# LIDO-HW_200_MCU_Peripherals_2.net
KiCad netlist of a schematic drawn in Altium Designer
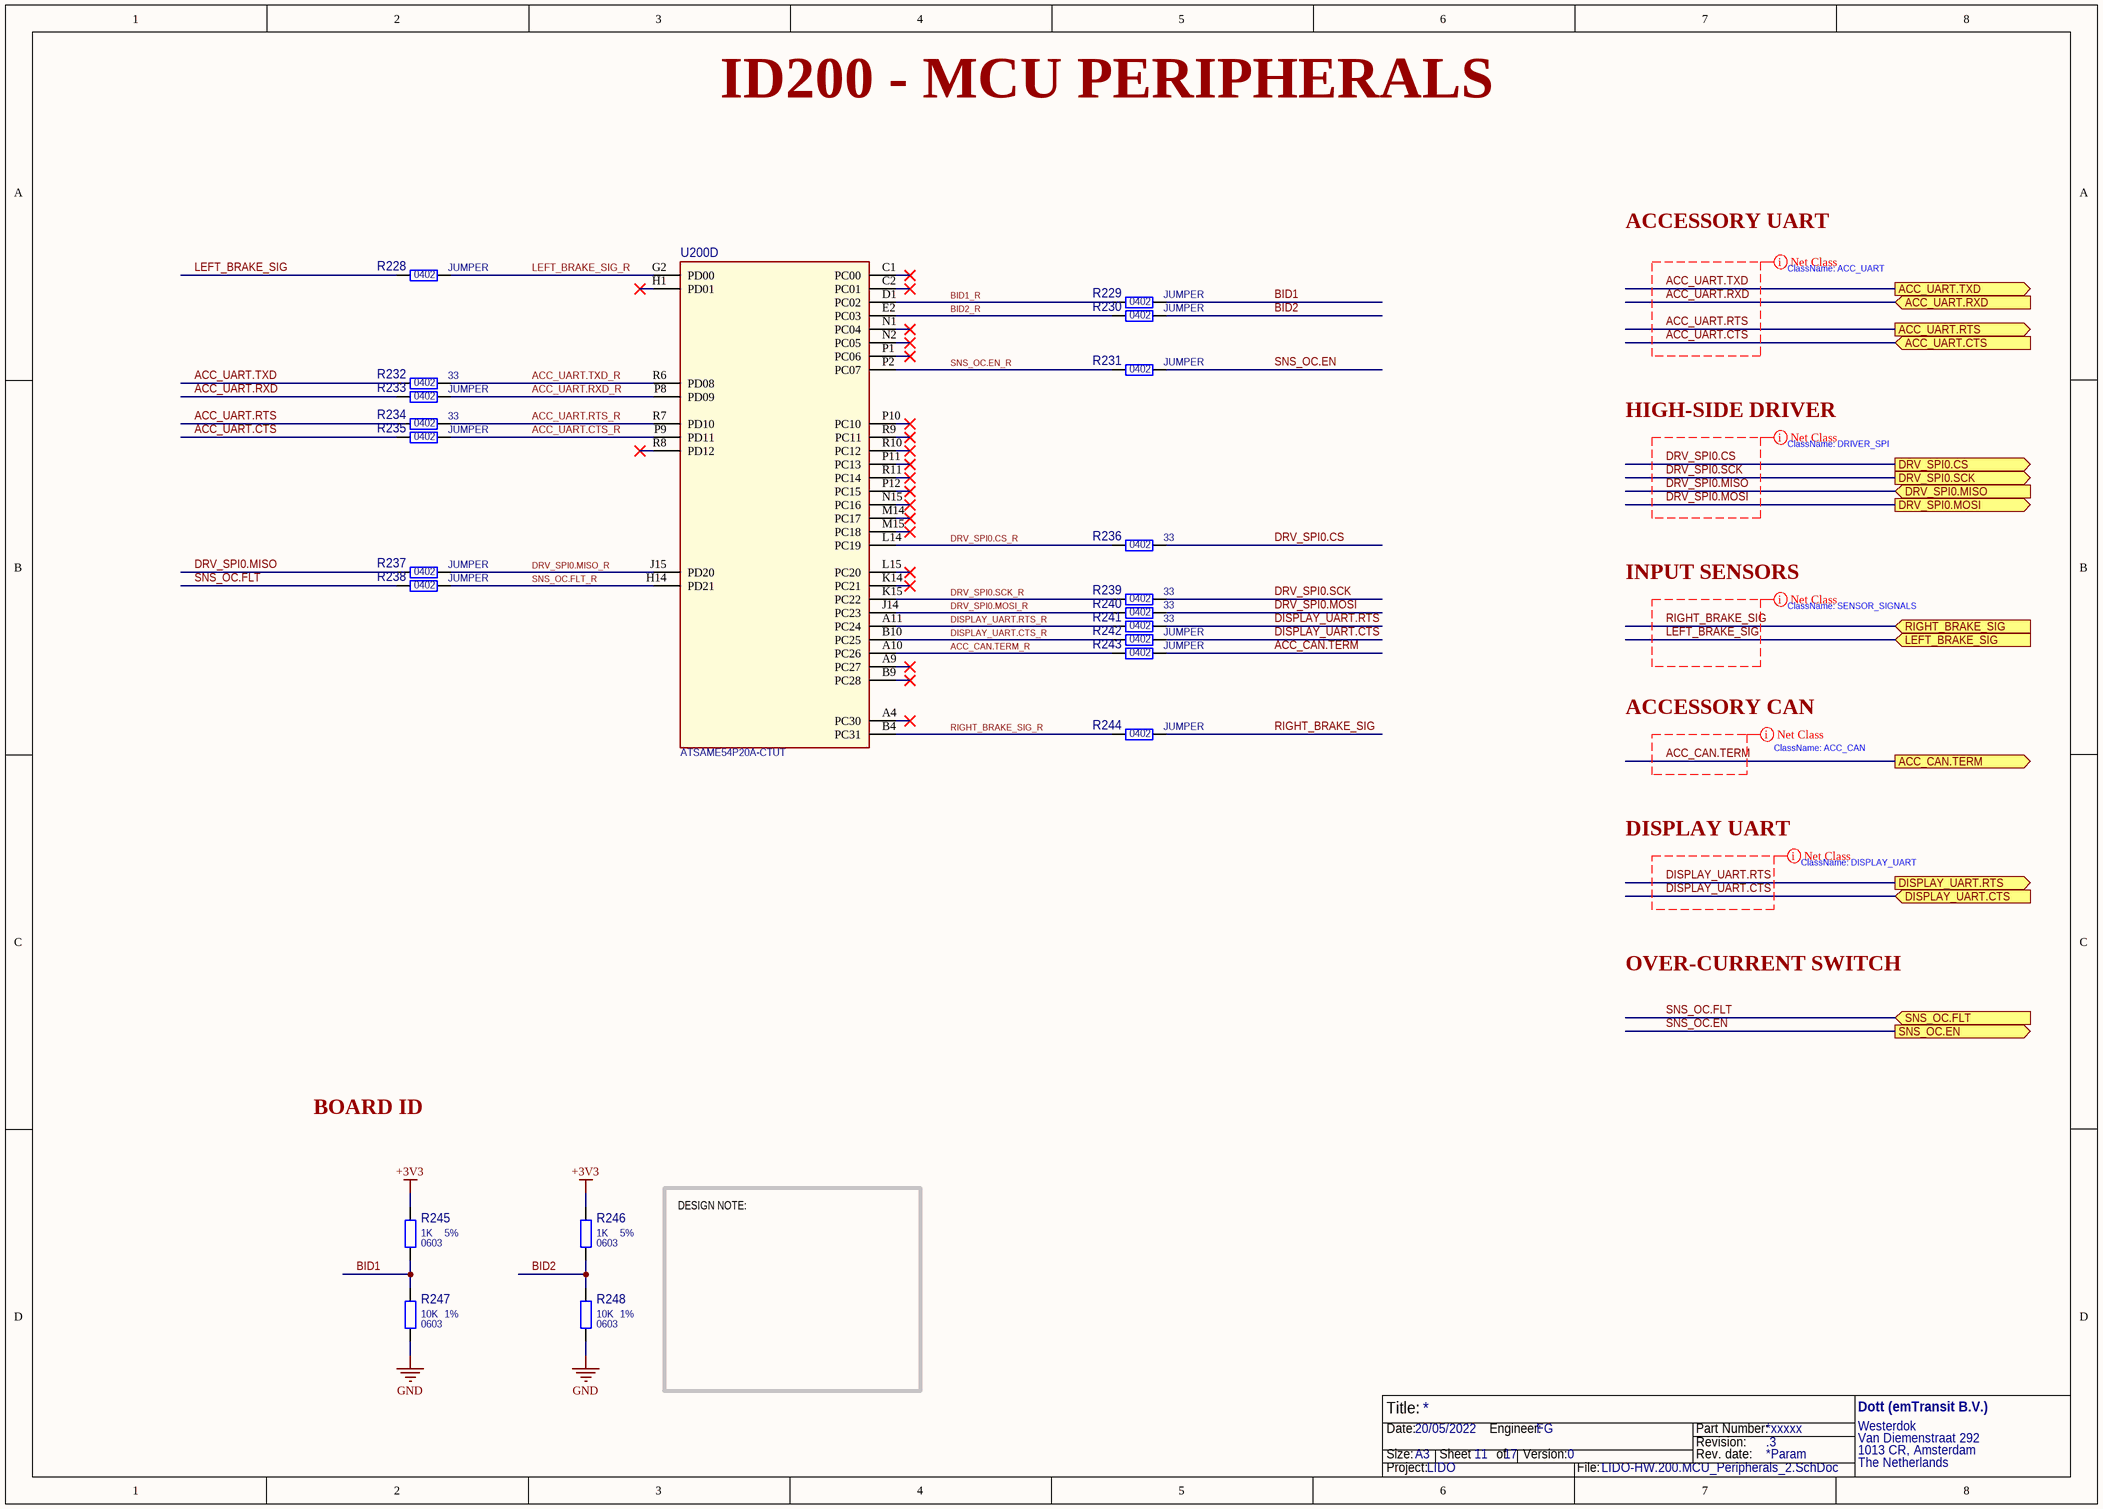
[diagram p0: LIDO-HW.200.MCU_Peripherals_2.SchDoc]

(export (version "E")
  (design (tool "Eeschema 10.0.6"))
  (components
    (comp (ref "R228")
      (value "JUMPER")
      (footprint "RES_0402_1005X40-N_YAGEO_A")
      (description "RES SMD 0 OHM JUMPER 1/10W 0402")
      (fields
        (field (name "MANUFACTURER PART NUMBER") "ERJ-2GE0R00X")
        (field (name "MANUFACTURER") "Panasonic Electronic Components")
        (field (name "PART PACKAGE") "0402")
      )
      (libsource (lib "DB_Library") (part "Resistor"))
    )
    (comp (ref "R229")
      (value "JUMPER")
      (footprint "RES_0402_1005X40-N_YAGEO_A")
      (description "RES SMD 0 OHM JUMPER 1/10W 0402")
      (fields
        (field (name "MANUFACTURER PART NUMBER") "ERJ-2GE0R00X")
        (field (name "MANUFACTURER") "Panasonic Electronic Components")
        (field (name "PART PACKAGE") "0402")
      )
      (libsource (lib "DB_Library") (part "Resistor"))
    )
    (comp (ref "R230")
      (value "JUMPER")
      (footprint "RES_0402_1005X40-N_YAGEO_A")
      (description "RES SMD 0 OHM JUMPER 1/10W 0402")
      (fields
        (field (name "MANUFACTURER PART NUMBER") "ERJ-2GE0R00X")
        (field (name "MANUFACTURER") "Panasonic Electronic Components")
        (field (name "PART PACKAGE") "0402")
      )
      (libsource (lib "DB_Library") (part "Resistor"))
    )
    (comp (ref "R231")
      (value "JUMPER")
      (footprint "RES_0402_1005X40-N_YAGEO_A")
      (description "RES SMD 0 OHM JUMPER 1/10W 0402")
      (fields
        (field (name "MANUFACTURER PART NUMBER") "ERJ-2GE0R00X")
        (field (name "MANUFACTURER") "Panasonic Electronic Components")
        (field (name "PART PACKAGE") "0402")
      )
      (libsource (lib "DB_Library") (part "Resistor"))
    )
    (comp (ref "R232")
      (value "33")
      (footprint "RES_0402_1005X40-N_YAGEO_A")
      (description "RES SMD 33 OHM 5% 1/10W 0402")
      (fields
        (field (name "MANUFACTURER PART NUMBER") "ERJ-2GEJ330X")
        (field (name "MANUFACTURER") "Panasonic Electronic Components")
        (field (name "PART PACKAGE") "0402")
      )
      (libsource (lib "DB_Library") (part "Resistor"))
    )
    (comp (ref "R233")
      (value "JUMPER")
      (footprint "RES_0402_1005X40-N_YAGEO_A")
      (description "RES SMD 0 OHM JUMPER 1/10W 0402")
      (fields
        (field (name "MANUFACTURER PART NUMBER") "ERJ-2GE0R00X")
        (field (name "MANUFACTURER") "Panasonic Electronic Components")
        (field (name "PART PACKAGE") "0402")
      )
      (libsource (lib "DB_Library") (part "Resistor"))
    )
    (comp (ref "R234")
      (value "33")
      (footprint "RES_0402_1005X40-N_YAGEO_A")
      (description "RES SMD 33 OHM 5% 1/10W 0402")
      (fields
        (field (name "MANUFACTURER PART NUMBER") "ERJ-2GEJ330X")
        (field (name "MANUFACTURER") "Panasonic Electronic Components")
        (field (name "PART PACKAGE") "0402")
      )
      (libsource (lib "DB_Library") (part "Resistor"))
    )
    (comp (ref "R235")
      (value "JUMPER")
      (footprint "RES_0402_1005X40-N_YAGEO_A")
      (description "RES SMD 0 OHM JUMPER 1/10W 0402")
      (fields
        (field (name "MANUFACTURER PART NUMBER") "ERJ-2GE0R00X")
        (field (name "MANUFACTURER") "Panasonic Electronic Components")
        (field (name "PART PACKAGE") "0402")
      )
      (libsource (lib "DB_Library") (part "Resistor"))
    )
    (comp (ref "R236")
      (value "33")
      (footprint "RES_0402_1005X40-N_YAGEO_A")
      (description "RES SMD 33 OHM 5% 1/10W 0402")
      (fields
        (field (name "MANUFACTURER PART NUMBER") "ERJ-2GEJ330X")
        (field (name "MANUFACTURER") "Panasonic Electronic Components")
        (field (name "PART PACKAGE") "0402")
      )
      (libsource (lib "DB_Library") (part "Resistor"))
    )
    (comp (ref "R237")
      (value "JUMPER")
      (footprint "RES_0402_1005X40-N_YAGEO_A")
      (description "RES SMD 0 OHM JUMPER 1/10W 0402")
      (fields
        (field (name "MANUFACTURER PART NUMBER") "ERJ-2GE0R00X")
        (field (name "MANUFACTURER") "Panasonic Electronic Components")
        (field (name "PART PACKAGE") "0402")
      )
      (libsource (lib "DB_Library") (part "Resistor"))
    )
    (comp (ref "R238")
      (value "JUMPER")
      (footprint "RES_0402_1005X40-N_YAGEO_A")
      (description "RES SMD 0 OHM JUMPER 1/10W 0402")
      (fields
        (field (name "MANUFACTURER PART NUMBER") "ERJ-2GE0R00X")
        (field (name "MANUFACTURER") "Panasonic Electronic Components")
        (field (name "PART PACKAGE") "0402")
      )
      (libsource (lib "DB_Library") (part "Resistor"))
    )
    (comp (ref "R239")
      (value "33")
      (footprint "RES_0402_1005X40-N_YAGEO_A")
      (description "RES SMD 33 OHM 5% 1/10W 0402")
      (fields
        (field (name "MANUFACTURER PART NUMBER") "ERJ-2GEJ330X")
        (field (name "MANUFACTURER") "Panasonic Electronic Components")
        (field (name "PART PACKAGE") "0402")
      )
      (libsource (lib "DB_Library") (part "Resistor"))
    )
    (comp (ref "R240")
      (value "33")
      (footprint "RES_0402_1005X40-N_YAGEO_A")
      (description "RES SMD 33 OHM 5% 1/10W 0402")
      (fields
        (field (name "MANUFACTURER PART NUMBER") "ERJ-2GEJ330X")
        (field (name "MANUFACTURER") "Panasonic Electronic Components")
        (field (name "PART PACKAGE") "0402")
      )
      (libsource (lib "DB_Library") (part "Resistor"))
    )
    (comp (ref "R241")
      (value "33")
      (footprint "RES_0402_1005X40-N_YAGEO_A")
      (description "RES SMD 33 OHM 5% 1/10W 0402")
      (fields
        (field (name "MANUFACTURER PART NUMBER") "ERJ-2GEJ330X")
        (field (name "MANUFACTURER") "Panasonic Electronic Components")
        (field (name "PART PACKAGE") "0402")
      )
      (libsource (lib "DB_Library") (part "Resistor"))
    )
    (comp (ref "R242")
      (value "JUMPER")
      (footprint "RES_0402_1005X40-N_YAGEO_A")
      (description "RES SMD 0 OHM JUMPER 1/10W 0402")
      (fields
        (field (name "MANUFACTURER PART NUMBER") "ERJ-2GE0R00X")
        (field (name "MANUFACTURER") "Panasonic Electronic Components")
        (field (name "PART PACKAGE") "0402")
      )
      (libsource (lib "DB_Library") (part "Resistor"))
    )
    (comp (ref "R243")
      (value "JUMPER")
      (footprint "RES_0402_1005X40-N_YAGEO_A")
      (description "RES SMD 0 OHM JUMPER 1/10W 0402")
      (fields
        (field (name "MANUFACTURER PART NUMBER") "ERJ-2GE0R00X")
        (field (name "MANUFACTURER") "Panasonic Electronic Components")
        (field (name "PART PACKAGE") "0402")
      )
      (libsource (lib "DB_Library") (part "Resistor"))
    )
    (comp (ref "R244")
      (value "JUMPER")
      (footprint "RES_0402_1005X40-N_YAGEO_A")
      (description "RES SMD 0 OHM JUMPER 1/10W 0402")
      (fields
        (field (name "MANUFACTURER PART NUMBER") "ERJ-2GE0R00X")
        (field (name "MANUFACTURER") "Panasonic Electronic Components")
        (field (name "PART PACKAGE") "0402")
      )
      (libsource (lib "DB_Library") (part "Resistor"))
    )
    (comp (ref "R245")
      (value "1K")
      (footprint "RES_0603_1608X60-N_YAGEO_A")
      (description "RES 1K OHM 5% 1/10W 0603")
      (fields
        (field (name "MANUFACTURER PART NUMBER") "RC0603JR-071KL")
        (field (name "MANUFACTURER") "YAGEO")
        (field (name "PART VALUE 2") "5%")
        (field (name "PART PACKAGE") "0603")
      )
      (libsource (lib "") (part "Resistor_1"))
    )
    (comp (ref "R246")
      (value "1K")
      (footprint "RES_0603_1608X60-N_YAGEO_A")
      (description "RES 1K OHM 5% 1/10W 0603")
      (fields
        (field (name "MANUFACTURER PART NUMBER") "RC0603JR-071KL")
        (field (name "MANUFACTURER") "YAGEO")
        (field (name "PART VALUE 2") "5%")
        (field (name "PART PACKAGE") "0603")
      )
      (libsource (lib "") (part "Resistor_1"))
    )
    (comp (ref "R247")
      (value "10K")
      (footprint "RES_0603_1608X60-N_YAGEO_A")
      (description "RES 10K OHM 1% 1/10W 0603")
      (fields
        (field (name "MANUFACTURER PART NUMBER") "RC0603FR-0710KL")
        (field (name "MANUFACTURER") "YAGEO")
        (field (name "PART VALUE 2") "1%")
        (field (name "PART PACKAGE") "0603")
      )
      (libsource (lib "") (part "Resistor_1"))
    )
    (comp (ref "R248")
      (value "10K")
      (footprint "RES_0603_1608X60-N_YAGEO_A")
      (description "RES 10K OHM 1% 1/10W 0603")
      (fields
        (field (name "MANUFACTURER PART NUMBER") "RC0603FR-0710KL")
        (field (name "MANUFACTURER") "YAGEO")
        (field (name "PART VALUE 2") "1%")
        (field (name "PART PACKAGE") "0603")
      )
      (libsource (lib "") (part "Resistor_1"))
    )
    (comp (ref "U200")
      (value "ATSAME54P20A-CTUT")
      (footprint "BGA120CP50_15X15_800X800X120B25-N_MICROCHIP_A")
      (fields (field (name "MANUFACTURER") "Microchip Technology") (field (name "OBSOLETE PART") "False"))
      (libsource (lib "DB_Library") (part "ATMEL_ATSAME54P20A-CT_A"))
    )
  )
  (nets
    (net (code "1") (name "+3V3") (class "Default")
      (node (ref "R245") (pin "2") (pinfunction "2_2") (pintype "passive"))
      (node (ref "R246") (pin "2") (pinfunction "2_2") (pintype "passive"))
    )
    (net (code "2") (name "/ACC_CAN.TERM") (class "Default")
      (node (ref "R243") (pin "2") (pinfunction "2_2") (pintype "passive"))
    )
    (net (code "3") (name "/ACC_CAN.TERM_R") (class "Default")
      (node (ref "R243") (pin "1") (pinfunction "1_1") (pintype "passive"))
      (node (ref "U200") (pin "A10") (pinfunction "PC26_A10") (pintype "passive"))
    )
    (net (code "4") (name "/ACC_UART.CTS") (class "Default")
      (node (ref "R235") (pin "1") (pinfunction "1_1") (pintype "passive"))
    )
    (net (code "5") (name "/ACC_UART.CTS_R") (class "Default")
      (node (ref "R235") (pin "2") (pinfunction "2_2") (pintype "passive"))
      (node (ref "U200") (pin "P9") (pinfunction "PD11_P9") (pintype "passive"))
    )
    (net (code "6") (name "/ACC_UART.RTS") (class "Default")
      (node (ref "R234") (pin "1") (pinfunction "1_1") (pintype "passive"))
    )
    (net (code "7") (name "/ACC_UART.RTS_R") (class "Default")
      (node (ref "R234") (pin "2") (pinfunction "2_2") (pintype "passive"))
      (node (ref "U200") (pin "R7") (pinfunction "PD10_R7") (pintype "passive"))
    )
    (net (code "8") (name "/ACC_UART.RXD") (class "Default")
      (node (ref "R233") (pin "1") (pinfunction "1_1") (pintype "passive"))
    )
    (net (code "9") (name "/ACC_UART.RXD_R") (class "Default")
      (node (ref "R233") (pin "2") (pinfunction "2_2") (pintype "passive"))
      (node (ref "U200") (pin "P8") (pinfunction "PD09_P8") (pintype "passive"))
    )
    (net (code "10") (name "/ACC_UART.TXD") (class "Default")
      (node (ref "R232") (pin "1") (pinfunction "1_1") (pintype "passive"))
    )
    (net (code "11") (name "/ACC_UART.TXD_R") (class "Default")
      (node (ref "R232") (pin "2") (pinfunction "2_2") (pintype "passive"))
      (node (ref "U200") (pin "R6") (pinfunction "PD08_R6") (pintype "passive"))
    )
    (net (code "12") (name "/BID1") (class "Default")
      (node (ref "R229") (pin "2") (pinfunction "2_2") (pintype "passive"))
      (node (ref "R245") (pin "1") (pinfunction "1_1") (pintype "passive"))
      (node (ref "R247") (pin "2") (pinfunction "2_2") (pintype "passive"))
    )
    (net (code "13") (name "/BID1_R") (class "Default")
      (node (ref "R229") (pin "1") (pinfunction "1_1") (pintype "passive"))
      (node (ref "U200") (pin "D1") (pinfunction "PC02_D1") (pintype "passive"))
    )
    (net (code "14") (name "/BID2") (class "Default")
      (node (ref "R230") (pin "2") (pinfunction "2_2") (pintype "passive"))
      (node (ref "R246") (pin "1") (pinfunction "1_1") (pintype "passive"))
      (node (ref "R248") (pin "2") (pinfunction "2_2") (pintype "passive"))
    )
    (net (code "15") (name "/BID2_R") (class "Default")
      (node (ref "R230") (pin "1") (pinfunction "1_1") (pintype "passive"))
      (node (ref "U200") (pin "E2") (pinfunction "PC03_E2") (pintype "passive"))
    )
    (net (code "16") (name "/DISPLAY_UART.CTS") (class "Default")
      (node (ref "R242") (pin "2") (pinfunction "2_2") (pintype "passive"))
    )
    (net (code "17") (name "/DISPLAY_UART.CTS_R") (class "Default")
      (node (ref "R242") (pin "1") (pinfunction "1_1") (pintype "passive"))
      (node (ref "U200") (pin "B10") (pinfunction "PC25_B10") (pintype "passive"))
    )
    (net (code "18") (name "/DISPLAY_UART.RTS") (class "Default")
      (node (ref "R241") (pin "2") (pinfunction "2_2") (pintype "passive"))
    )
    (net (code "19") (name "/DISPLAY_UART.RTS_R") (class "Default")
      (node (ref "R241") (pin "1") (pinfunction "1_1") (pintype "passive"))
      (node (ref "U200") (pin "A11") (pinfunction "PC24_A11") (pintype "passive"))
    )
    (net (code "20") (name "/DRV_SPI0.CS") (class "Default")
      (node (ref "R236") (pin "2") (pinfunction "2_2") (pintype "passive"))
    )
    (net (code "21") (name "/DRV_SPI0.CS_R") (class "Default")
      (node (ref "R236") (pin "1") (pinfunction "1_1") (pintype "passive"))
      (node (ref "U200") (pin "L14") (pinfunction "PC19_L14") (pintype "passive"))
    )
    (net (code "22") (name "/DRV_SPI0.MISO") (class "Default")
      (node (ref "R237") (pin "1") (pinfunction "1_1") (pintype "passive"))
    )
    (net (code "23") (name "/DRV_SPI0.MISO_R") (class "Default")
      (node (ref "R237") (pin "2") (pinfunction "2_2") (pintype "passive"))
      (node (ref "U200") (pin "J15") (pinfunction "PD20_J15") (pintype "passive"))
    )
    (net (code "24") (name "/DRV_SPI0.MOSI") (class "Default")
      (node (ref "R240") (pin "2") (pinfunction "2_2") (pintype "passive"))
    )
    (net (code "25") (name "/DRV_SPI0.MOSI_R") (class "Default")
      (node (ref "R240") (pin "1") (pinfunction "1_1") (pintype "passive"))
      (node (ref "U200") (pin "J14") (pinfunction "PC23_J14") (pintype "passive"))
    )
    (net (code "26") (name "/DRV_SPI0.SCK") (class "Default")
      (node (ref "R239") (pin "2") (pinfunction "2_2") (pintype "passive"))
    )
    (net (code "27") (name "/DRV_SPI0.SCK_R") (class "Default")
      (node (ref "R239") (pin "1") (pinfunction "1_1") (pintype "passive"))
      (node (ref "U200") (pin "K15") (pinfunction "PC22_K15") (pintype "passive"))
    )
    (net (code "28") (name "/LEFT_BRAKE_SIG") (class "Default")
      (node (ref "R228") (pin "1") (pinfunction "1_1") (pintype "passive"))
    )
    (net (code "29") (name "/LEFT_BRAKE_SIG_R") (class "Default")
      (node (ref "R228") (pin "2") (pinfunction "2_2") (pintype "passive"))
      (node (ref "U200") (pin "G2") (pinfunction "PD00_G2") (pintype "passive"))
    )
    (net (code "30") (name "/RIGHT_BRAKE_SIG") (class "Default")
      (node (ref "R244") (pin "2") (pinfunction "2_2") (pintype "passive"))
    )
    (net (code "31") (name "/RIGHT_BRAKE_SIG_R") (class "Default")
      (node (ref "R244") (pin "1") (pinfunction "1_1") (pintype "passive"))
      (node (ref "U200") (pin "B4") (pinfunction "PC31_B4") (pintype "passive"))
    )
    (net (code "32") (name "/SNS_OC.EN") (class "Default")
      (node (ref "R231") (pin "2") (pinfunction "2_2") (pintype "passive"))
    )
    (net (code "33") (name "/SNS_OC.EN_R") (class "Default")
      (node (ref "R231") (pin "1") (pinfunction "1_1") (pintype "passive"))
      (node (ref "U200") (pin "P2") (pinfunction "PC07_P2") (pintype "passive"))
    )
    (net (code "34") (name "/SNS_OC.FLT") (class "Default")
      (node (ref "R238") (pin "1") (pinfunction "1_1") (pintype "passive"))
    )
    (net (code "35") (name "/SNS_OC.FLT_R") (class "Default")
      (node (ref "R238") (pin "2") (pinfunction "2_2") (pintype "passive"))
      (node (ref "U200") (pin "H14") (pinfunction "PD21_H14") (pintype "passive"))
    )
    (net (code "36") (name "GND") (class "Default")
      (node (ref "R247") (pin "1") (pinfunction "1_1") (pintype "passive"))
      (node (ref "R248") (pin "1") (pinfunction "1_1") (pintype "passive"))
    )
    (net (code "37") (name "unconnected-(U200D-PC00-PadC1)") (class "Default")
      (node (ref "U200") (pin "C1") (pinfunction "PC00_C1") (pintype "passive+no_connect"))
    )
    (net (code "38") (name "unconnected-(U200D-PC01-PadC2)") (class "Default")
      (node (ref "U200") (pin "C2") (pinfunction "PC01_C2") (pintype "passive+no_connect"))
    )
    (net (code "39") (name "unconnected-(U200D-PC04-PadN1)") (class "Default")
      (node (ref "U200") (pin "N1") (pinfunction "PC04_N1") (pintype "passive+no_connect"))
    )
    (net (code "40") (name "unconnected-(U200D-PC05-PadN2)") (class "Default")
      (node (ref "U200") (pin "N2") (pinfunction "PC05_N2") (pintype "passive+no_connect"))
    )
    (net (code "41") (name "unconnected-(U200D-PC06-PadP1)") (class "Default")
      (node (ref "U200") (pin "P1") (pinfunction "PC06_P1") (pintype "passive+no_connect"))
    )
    (net (code "42") (name "unconnected-(U200D-PC10-PadP10)") (class "Default")
      (node (ref "U200") (pin "P10") (pinfunction "PC10_P10") (pintype "passive+no_connect"))
    )
    (net (code "43") (name "unconnected-(U200D-PC11-PadR9)") (class "Default")
      (node (ref "U200") (pin "R9") (pinfunction "PC11_R9") (pintype "passive+no_connect"))
    )
    (net (code "44") (name "unconnected-(U200D-PC12-PadR10)") (class "Default")
      (node (ref "U200") (pin "R10") (pinfunction "PC12_R10") (pintype "passive+no_connect"))
    )
    (net (code "45") (name "unconnected-(U200D-PC13-PadP11)") (class "Default")
      (node (ref "U200") (pin "P11") (pinfunction "PC13_P11") (pintype "passive+no_connect"))
    )
    (net (code "46") (name "unconnected-(U200D-PC14-PadR11)") (class "Default")
      (node (ref "U200") (pin "R11") (pinfunction "PC14_R11") (pintype "passive+no_connect"))
    )
    (net (code "47") (name "unconnected-(U200D-PC15-PadP12)") (class "Default")
      (node (ref "U200") (pin "P12") (pinfunction "PC15_P12") (pintype "passive+no_connect"))
    )
    (net (code "48") (name "unconnected-(U200D-PC16-PadN15)") (class "Default")
      (node (ref "U200") (pin "N15") (pinfunction "PC16_N15") (pintype "passive+no_connect"))
    )
    (net (code "49") (name "unconnected-(U200D-PC17-PadM14)") (class "Default")
      (node (ref "U200") (pin "M14") (pinfunction "PC17_M14") (pintype "passive+no_connect"))
    )
    (net (code "50") (name "unconnected-(U200D-PC18-PadM15)") (class "Default")
      (node (ref "U200") (pin "M15") (pinfunction "PC18_M15") (pintype "passive+no_connect"))
    )
    (net (code "51") (name "unconnected-(U200D-PC20-PadL15)") (class "Default")
      (node (ref "U200") (pin "L15") (pinfunction "PC20_L15") (pintype "passive+no_connect"))
    )
    (net (code "52") (name "unconnected-(U200D-PC21-PadK14)") (class "Default")
      (node (ref "U200") (pin "K14") (pinfunction "PC21_K14") (pintype "passive+no_connect"))
    )
    (net (code "53") (name "unconnected-(U200D-PC27-PadA9)") (class "Default")
      (node (ref "U200") (pin "A9") (pinfunction "PC27_A9") (pintype "passive+no_connect"))
    )
    (net (code "54") (name "unconnected-(U200D-PC28-PadB9)") (class "Default")
      (node (ref "U200") (pin "B9") (pinfunction "PC28_B9") (pintype "passive+no_connect"))
    )
    (net (code "55") (name "unconnected-(U200D-PC30-PadA4)") (class "Default")
      (node (ref "U200") (pin "A4") (pinfunction "PC30_A4") (pintype "passive+no_connect"))
    )
    (net (code "56") (name "unconnected-(U200D-PD01-PadH1)") (class "Default")
      (node (ref "U200") (pin "H1") (pinfunction "PD01_H1") (pintype "passive+no_connect"))
    )
    (net (code "57") (name "unconnected-(U200D-PD12-PadR8)") (class "Default")
      (node (ref "U200") (pin "R8") (pinfunction "PD12_R8") (pintype "passive+no_connect"))
    )
  )
)
